# schema.net
KiCad netlist of a schematic drawn in EAGLE
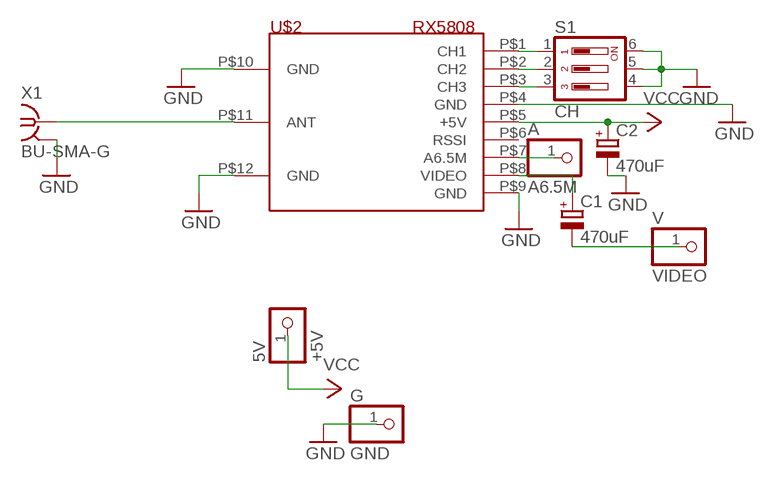
[diagram p0: schematic, sheet 1]

(export (version "E")
  (design (tool "Eeschema 10.0.6"))
  (components
    (comp (ref "5V")
      (value "+5V")
      (footprint "eagle-import:1X01")
      (libsource (lib "eagle-import") (part "PINHD-1X1"))
    )
    (comp (ref "A")
      (value "A6.5M")
      (footprint "eagle-import:1X01")
      (libsource (lib "eagle-import") (part "PINHD-1X1"))
    )
    (comp (ref "C1")
      (value "470uF")
      (footprint "eagle-import:E3,5-8")
      (libsource (lib "eagle-import") (part "CPOL-EUE3.5-8"))
    )
    (comp (ref "C2")
      (value "470uF")
      (footprint "eagle-import:E3,5-8")
      (libsource (lib "eagle-import") (part "CPOL-EUE3.5-8"))
    )
    (comp (ref "G")
      (value "GND")
      (footprint "eagle-import:1X01")
      (libsource (lib "eagle-import") (part "PINHD-1X1"))
    )
    (comp (ref "S1")
      (value "CH")
      (footprint "eagle-import:DS-03")
      (libsource (lib "eagle-import") (part "DS03"))
    )
    (comp (ref "U$2")
      (value "RX5808")
      (footprint "eagle-import:RX5808")
      (libsource (lib "eagle-import") (part "RX5808"))
    )
    (comp (ref "V")
      (value "VIDEO")
      (footprint "eagle-import:1X01")
      (libsource (lib "eagle-import") (part "PINHD-1X1"))
    )
    (comp (ref "X1")
      (value "BU-SMA-G")
      (footprint "eagle-import:BU-SMA-G")
      (libsource (lib "eagle-import") (part "BU-SMA-G"))
    )
  )
  (nets
    (net (code "1") (name "GND") (class "Default")
      (node (ref "C2") (pin "-") (pinfunction "-_-") (pintype "passive"))
      (node (ref "G") (pin "1") (pinfunction "1_1") (pintype "passive"))
      (node (ref "S1") (pin "4") (pinfunction "4_4") (pintype "passive"))
      (node (ref "S1") (pin "5") (pinfunction "5_5") (pintype "passive"))
      (node (ref "S1") (pin "6") (pinfunction "6_6") (pintype "passive"))
      (node (ref "U$2") (pin "P$10") (pinfunction "GND_P$10") (pintype "bidirectional"))
      (node (ref "U$2") (pin "P$12") (pinfunction "GND_P$12") (pintype "bidirectional"))
      (node (ref "U$2") (pin "P$4") (pinfunction "GND_P$4") (pintype "bidirectional"))
      (node (ref "U$2") (pin "P$9") (pinfunction "GND_P$9") (pintype "bidirectional"))
      (node (ref "X1") (pin "2") (pinfunction "2_2") (pintype "passive"))
      (node (ref "X1") (pin "3") (pinfunction "2_3") (pintype "passive"))
      (node (ref "X1") (pin "4") (pinfunction "2_4") (pintype "passive"))
      (node (ref "X1") (pin "5") (pinfunction "2_5") (pintype "passive"))
    )
    (net (code "2") (name "Net-(C1-Pad-)") (class "Default")
      (node (ref "C1") (pin "-") (pinfunction "-_-") (pintype "passive"))
      (node (ref "V") (pin "1") (pinfunction "1_1") (pintype "passive"))
    )
    (net (code "3") (name "Net-(U$2-A6.5M)") (class "Default")
      (node (ref "A") (pin "1") (pinfunction "1_1") (pintype "passive"))
      (node (ref "U$2") (pin "P$7") (pinfunction "A6.5M_P$7") (pintype "bidirectional"))
    )
    (net (code "4") (name "Net-(U$2-ANT)") (class "Default")
      (node (ref "U$2") (pin "P$11") (pinfunction "ANT_P$11") (pintype "bidirectional"))
      (node (ref "X1") (pin "1") (pinfunction "1_1") (pintype "passive"))
    )
    (net (code "5") (name "Net-(U$2-CH1)") (class "Default")
      (node (ref "S1") (pin "1") (pinfunction "1_1") (pintype "passive"))
      (node (ref "U$2") (pin "P$1") (pinfunction "CH1_P$1") (pintype "bidirectional"))
    )
    (net (code "6") (name "Net-(U$2-CH2)") (class "Default")
      (node (ref "S1") (pin "2") (pinfunction "2_2") (pintype "passive"))
      (node (ref "U$2") (pin "P$2") (pinfunction "CH2_P$2") (pintype "bidirectional"))
    )
    (net (code "7") (name "Net-(U$2-CH3)") (class "Default")
      (node (ref "S1") (pin "3") (pinfunction "3_3") (pintype "passive"))
      (node (ref "U$2") (pin "P$3") (pinfunction "CH3_P$3") (pintype "bidirectional"))
    )
    (net (code "8") (name "Net-(U$2-VIDEO)") (class "Default")
      (node (ref "C1") (pin "+") (pinfunction "+_+") (pintype "passive"))
      (node (ref "U$2") (pin "P$8") (pinfunction "VIDEO_P$8") (pintype "bidirectional"))
    )
    (net (code "9") (name "VCC") (class "Default")
      (node (ref "5V") (pin "1") (pinfunction "1_1") (pintype "passive"))
      (node (ref "C2") (pin "+") (pinfunction "+_+") (pintype "passive"))
      (node (ref "U$2") (pin "P$5") (pinfunction "+5V_P$5") (pintype "bidirectional"))
    )
    (net (code "10") (name "unconnected-(U$2-RSSI-PadP$6)") (class "Default")
      (node (ref "U$2") (pin "P$6") (pinfunction "RSSI_P$6") (pintype "bidirectional"))
    )
  )
)
